# Nusbio_smd.net
KiCad netlist of a schematic drawn in EAGLE
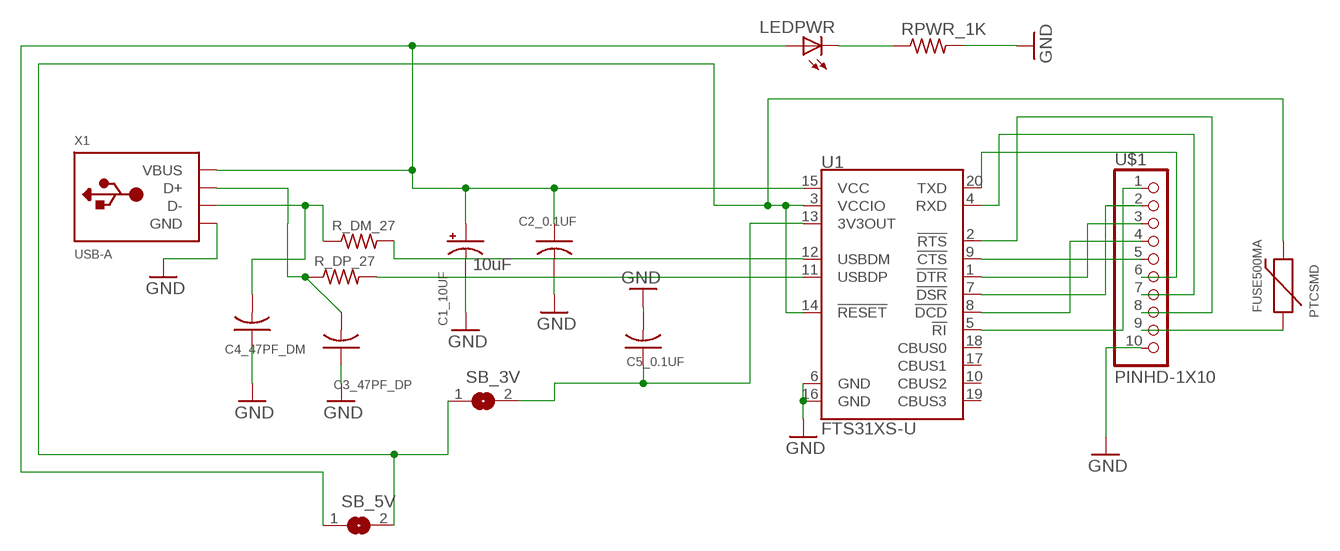
[diagram p0: schematic, sheet 1]

(export (version "E")
  (design (tool "Eeschema 10.0.6"))
  (components
    (comp (ref "C1_10UF")
      (value "10uF")
      (footprint "eagle-import:EIA3216")
      (libsource (lib "eagle-import") (part "10UF-16V-10%(TANT)"))
    )
    (comp (ref "C2_0.1UF")
      (value "C-USC1206")
      (footprint "eagle-import:C1206")
      (libsource (lib "eagle-import") (part "C-USC1206"))
    )
    (comp (ref "C3_47PF_DP")
      (value "C-USC1206")
      (footprint "eagle-import:C1206")
      (libsource (lib "eagle-import") (part "C-USC1206"))
    )
    (comp (ref "C4_47PF_DM")
      (value "C-USC1206")
      (footprint "eagle-import:C1206")
      (libsource (lib "eagle-import") (part "C-USC1206"))
    )
    (comp (ref "C5_0.1UF")
      (value "C-USC1206")
      (footprint "eagle-import:C1206")
      (libsource (lib "eagle-import") (part "C-USC1206"))
    )
    (comp (ref "FUSE500MA")
      (value "PTCSMD")
      (footprint "eagle-import:PTC-1206")
      (libsource (lib "eagle-import") (part "PTCSMD"))
    )
    (comp (ref "LEDPWR")
      (value "LEDCHIPLED_0805")
      (footprint "eagle-import:CHIPLED_0805")
      (libsource (lib "eagle-import") (part "LEDCHIPLED_0805"))
    )
    (comp (ref "RPWR_1K")
      (value "R-US_R0805")
      (footprint "eagle-import:R0805")
      (libsource (lib "eagle-import") (part "R-US_R0805"))
    )
    (comp (ref "R_DM_27")
      (value "R-US_R0805")
      (footprint "eagle-import:R0805")
      (libsource (lib "eagle-import") (part "R-US_R0805"))
    )
    (comp (ref "R_DP_27")
      (value "R-US_R0805")
      (footprint "eagle-import:R0805")
      (libsource (lib "eagle-import") (part "R-US_R0805"))
    )
    (comp (ref "SB_3V")
      (value "SOLDERJUMPERREFLOW")
      (footprint "eagle-import:SOLDERJUMPER_REFLOW")
      (libsource (lib "eagle-import") (part "SOLDERJUMPERREFLOW"))
    )
    (comp (ref "SB_5V")
      (value "SOLDERJUMPERREFLOW")
      (footprint "eagle-import:SOLDERJUMPER_REFLOW")
      (libsource (lib "eagle-import") (part "SOLDERJUMPERREFLOW"))
    )
    (comp (ref "U$1")
      (value "PINHD-1X10")
      (footprint "eagle-import:1X10-BIG")
      (libsource (lib "eagle-import") (part "PINHD-1X10"))
    )
    (comp (ref "U1")
      (value "FTS31XS-U")
      (footprint "eagle-import:SSOP20_L")
      (libsource (lib "eagle-import") (part "FT231XS"))
    )
    (comp (ref "X1")
      (value "USB-A")
      (footprint "eagle-import:MOLEX_480371000")
      (libsource (lib "eagle-import") (part "USB-A"))
    )
  )
  (nets
    (net (code "1") (name "GND") (class "Default")
      (node (ref "C1_10UF") (pin "C") (pinfunction "-_C") (pintype "passive"))
      (node (ref "C2_0.1UF") (pin "2") (pinfunction "2_2") (pintype "passive"))
      (node (ref "C3_47PF_DP") (pin "1") (pinfunction "1_1") (pintype "passive"))
      (node (ref "C4_47PF_DM") (pin "1") (pinfunction "1_1") (pintype "passive"))
      (node (ref "C5_0.1UF") (pin "2") (pinfunction "2_2") (pintype "passive"))
      (node (ref "RPWR_1K") (pin "2") (pinfunction "2_2") (pintype "passive"))
      (node (ref "U$1") (pin "10") (pinfunction "10_10") (pintype "passive"))
      (node (ref "U1") (pin "16") (pinfunction "GND_16") (pintype "bidirectional"))
      (node (ref "U1") (pin "6") (pinfunction "GND_6") (pintype "bidirectional"))
      (node (ref "X1") (pin "4") (pinfunction "GND_4") (pintype "power_in"))
    )
    (net (code "2") (name "Net-(C1_10UF-+)") (class "Default")
      (node (ref "C1_10UF") (pin "A") (pinfunction "+_A") (pintype "passive"))
      (node (ref "C2_0.1UF") (pin "1") (pinfunction "1_1") (pintype "passive"))
      (node (ref "LEDPWR") (pin "A") (pinfunction "A_A") (pintype "passive"))
      (node (ref "SB_5V") (pin "1") (pinfunction "1_1") (pintype "passive"))
      (node (ref "U1") (pin "15") (pinfunction "VCC_15") (pintype "bidirectional"))
      (node (ref "X1") (pin "1") (pinfunction "VBUS_1") (pintype "power_in"))
    )
    (net (code "3") (name "Net-(FUSE500MA-Pad1)") (class "Default")
      (node (ref "FUSE500MA") (pin "1") (pinfunction "1_1") (pintype "bidirectional"))
      (node (ref "U$1") (pin "9") (pinfunction "9_9") (pintype "passive"))
    )
    (net (code "4") (name "Net-(LEDPWR-PadC)") (class "Default")
      (node (ref "LEDPWR") (pin "C") (pinfunction "C_C") (pintype "passive"))
      (node (ref "RPWR_1K") (pin "1") (pinfunction "1_1") (pintype "passive"))
    )
    (net (code "5") (name "Net-(U1-3V3OUT)") (class "Default")
      (node (ref "C5_0.1UF") (pin "1") (pinfunction "1_1") (pintype "passive"))
      (node (ref "SB_3V") (pin "2") (pinfunction "2_2") (pintype "passive"))
      (node (ref "U1") (pin "13") (pinfunction "3V3OUT_13") (pintype "bidirectional"))
    )
    (net (code "6") (name "Net-(U1-RXD)") (class "Default")
      (node (ref "U$1") (pin "7") (pinfunction "7_7") (pintype "passive"))
      (node (ref "U1") (pin "4") (pinfunction "RXD_4") (pintype "bidirectional"))
    )
    (net (code "7") (name "Net-(U1-TXD)") (class "Default")
      (node (ref "U$1") (pin "6") (pinfunction "6_6") (pintype "passive"))
      (node (ref "U1") (pin "20") (pinfunction "TXD_20") (pintype "bidirectional"))
    )
    (net (code "8") (name "Net-(U1-USBDM)") (class "Default")
      (node (ref "R_DM_27") (pin "2") (pinfunction "2_2") (pintype "passive"))
      (node (ref "U1") (pin "12") (pinfunction "USBDM_12") (pintype "bidirectional"))
    )
    (net (code "9") (name "Net-(U1-USBDP)") (class "Default")
      (node (ref "R_DP_27") (pin "2") (pinfunction "2_2") (pintype "passive"))
      (node (ref "U1") (pin "11") (pinfunction "USBDP_11") (pintype "bidirectional"))
    )
    (net (code "10") (name "Net-(U1-VCCIO)") (class "Default")
      (node (ref "FUSE500MA") (pin "2") (pinfunction "2_2") (pintype "bidirectional"))
      (node (ref "SB_3V") (pin "1") (pinfunction "1_1") (pintype "passive"))
      (node (ref "SB_5V") (pin "2") (pinfunction "2_2") (pintype "passive"))
      (node (ref "U1") (pin "14") (pinfunction "~{RESET}_14") (pintype "bidirectional"))
      (node (ref "U1") (pin "3") (pinfunction "VCCIO_3") (pintype "bidirectional"))
    )
    (net (code "11") (name "Net-(U1-~{CTS})") (class "Default")
      (node (ref "U$1") (pin "5") (pinfunction "5_5") (pintype "passive"))
      (node (ref "U1") (pin "9") (pinfunction "~{CTS}_9") (pintype "bidirectional"))
    )
    (net (code "12") (name "Net-(U1-~{DCD})") (class "Default")
      (node (ref "U$1") (pin "4") (pinfunction "4_4") (pintype "passive"))
      (node (ref "U1") (pin "8") (pinfunction "~{DCD}_8") (pintype "bidirectional"))
    )
    (net (code "13") (name "Net-(U1-~{DSR})") (class "Default")
      (node (ref "U$1") (pin "2") (pinfunction "2_2") (pintype "passive"))
      (node (ref "U1") (pin "7") (pinfunction "~{DSR}_7") (pintype "bidirectional"))
    )
    (net (code "14") (name "Net-(U1-~{DTR})") (class "Default")
      (node (ref "U$1") (pin "3") (pinfunction "3_3") (pintype "passive"))
      (node (ref "U1") (pin "1") (pinfunction "~{DTR}_1") (pintype "bidirectional"))
    )
    (net (code "15") (name "Net-(U1-~{RI})") (class "Default")
      (node (ref "U$1") (pin "1") (pinfunction "1_1") (pintype "passive"))
      (node (ref "U1") (pin "5") (pinfunction "~{RI}_5") (pintype "bidirectional"))
    )
    (net (code "16") (name "Net-(U1-~{RTS})") (class "Default")
      (node (ref "U$1") (pin "8") (pinfunction "8_8") (pintype "passive"))
      (node (ref "U1") (pin "2") (pinfunction "~{RTS}_2") (pintype "bidirectional"))
    )
    (net (code "17") (name "Net-(X1-D+)") (class "Default")
      (node (ref "C3_47PF_DP") (pin "2") (pinfunction "2_2") (pintype "passive"))
      (node (ref "R_DP_27") (pin "1") (pinfunction "1_1") (pintype "passive"))
      (node (ref "X1") (pin "3") (pinfunction "D+_3") (pintype "bidirectional"))
    )
    (net (code "18") (name "Net-(X1-D-)") (class "Default")
      (node (ref "C4_47PF_DM") (pin "2") (pinfunction "2_2") (pintype "passive"))
      (node (ref "R_DM_27") (pin "1") (pinfunction "1_1") (pintype "passive"))
      (node (ref "X1") (pin "2") (pinfunction "D-_2") (pintype "bidirectional"))
    )
    (net (code "19") (name "unconnected-(U1-CBUS0-Pad18)") (class "Default")
      (node (ref "U1") (pin "18") (pinfunction "CBUS0_18") (pintype "bidirectional"))
    )
    (net (code "20") (name "unconnected-(U1-CBUS1-Pad17)") (class "Default")
      (node (ref "U1") (pin "17") (pinfunction "CBUS1_17") (pintype "bidirectional"))
    )
    (net (code "21") (name "unconnected-(U1-CBUS2-Pad10)") (class "Default")
      (node (ref "U1") (pin "10") (pinfunction "CBUS2_10") (pintype "bidirectional"))
    )
    (net (code "22") (name "unconnected-(U1-CBUS3-Pad19)") (class "Default")
      (node (ref "U1") (pin "19") (pinfunction "CBUS3_19") (pintype "bidirectional"))
    )
  )
)
